# Bank_13_Bank_15_Bank_16.net
KiCad netlist of a schematic drawn in Altium Designer
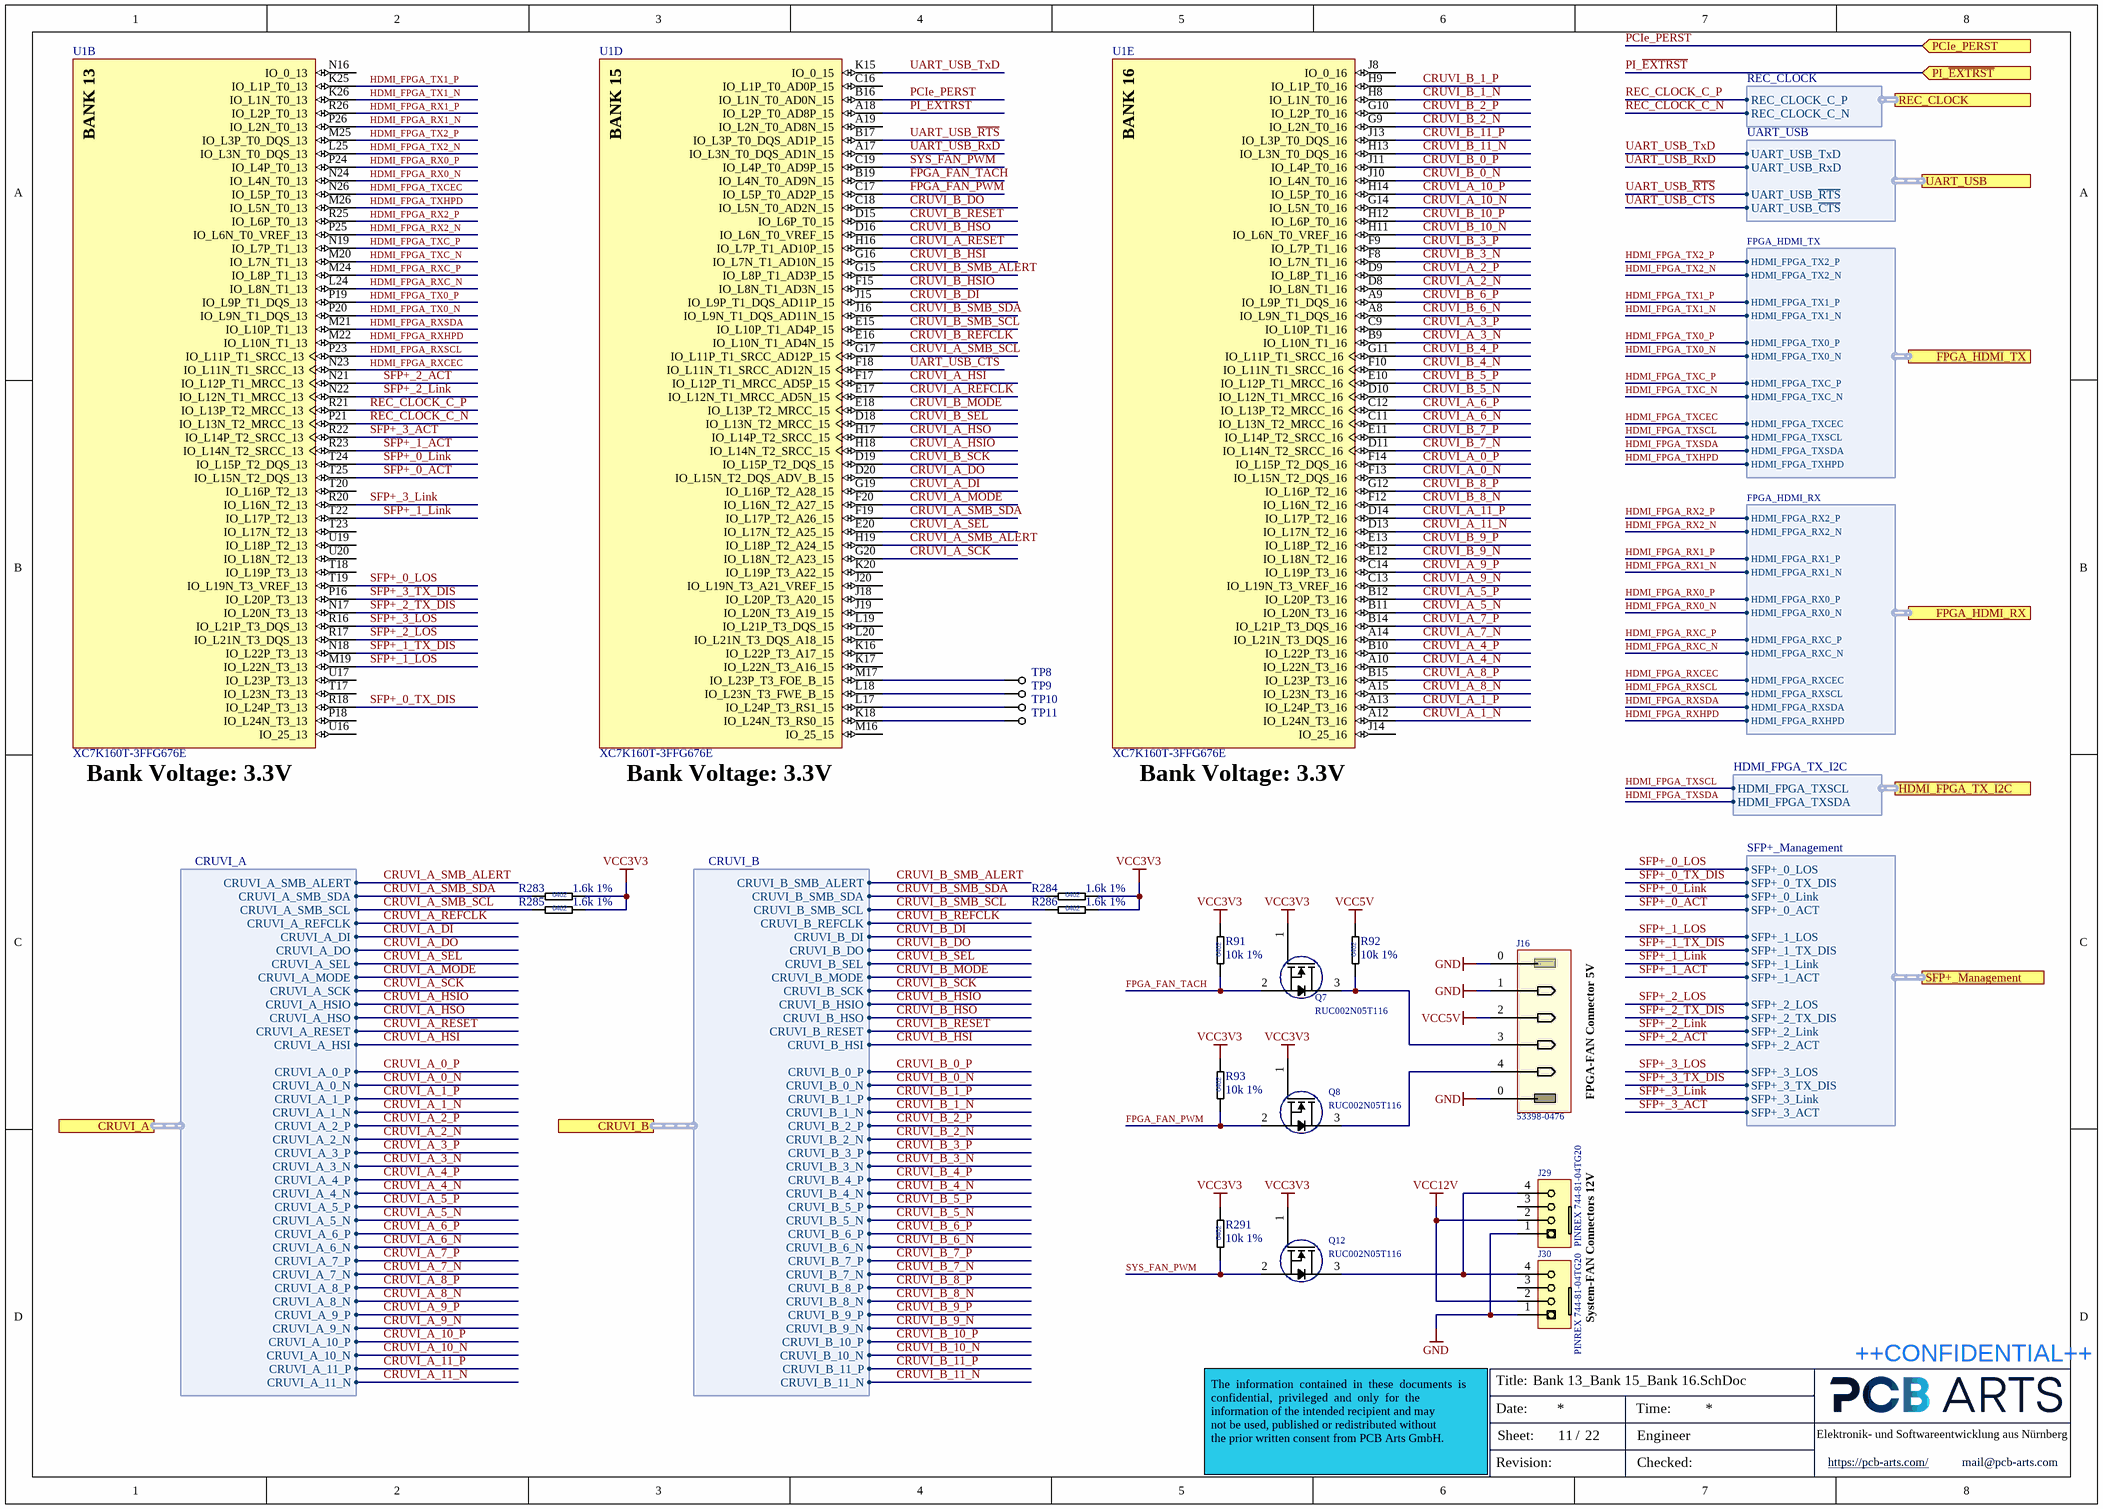
[diagram p0: Bank 13_Bank 15_Bank 16.SchDoc]

(export (version "E")
  (design (tool "Eeschema 10.0.6"))
  (components
    (comp (ref "J16")
      (value "53398-0476")
      (footprint "Conn:Molex 53398-0476")
      (description "1.25mm Pitch, PicoBlade PCB Header, Single Row, horizontal, SMD, 4 Pin")
      (libsource (lib "Conn") (part "53398-0476_1.25mm Pitch, PicoBlade PCB Header, Single Row, horizontal, SMD, 4 Pin"))
    )
    (comp (ref "J29")
      (value "PINREX 744-81-04TG20")
      (footprint "conn:PINREX 744-81-04TG20")
      (description "FAN Connector header 2.54mm 4Pol")
      (libsource (lib "Conn") (part "FAN Connector header 2.54mm 4Pol Pinrex 744-81-04TG20"))
    )
    (comp (ref "J30")
      (value "PINREX 744-81-04TG20")
      (footprint "conn:PINREX 744-81-04TG20")
      (description "FAN Connector header 2.54mm 4Pol")
      (libsource (lib "Conn") (part "FAN Connector header 2.54mm 4Pol Pinrex 744-81-04TG20"))
    )
    (comp (ref "Q7")
      (value "RUC002N05T116")
      (footprint "trans:SOT95P251X112-3N")
      (description "MOSFET N-Ch 1.2 VGS Spec")
      (libsource (lib "Trans") (part "RUC002N05T116_MOSFET N-Ch 1.2 VGS Spec"))
    )
    (comp (ref "Q8")
      (value "RUC002N05T116")
      (footprint "trans:SOT95P251X112-3N")
      (description "MOSFET N-Ch 1.2 VGS Spec")
      (libsource (lib "Trans") (part "RUC002N05T116_MOSFET N-Ch 1.2 VGS Spec"))
    )
    (comp (ref "Q12")
      (value "RUC002N05T116")
      (footprint "trans:SOT95P251X112-3N")
      (description "MOSFET N-Ch 1.2 VGS Spec")
      (libsource (lib "Trans") (part "RUC002N05T116_MOSFET N-Ch 1.2 VGS Spec"))
    )
    (comp (ref "R91")
      (value "10k 1%")
      (footprint "Res:RES_0402_L")
      (description "Thick Film Resistors - SMD 10kOhm 1%")
      (libsource (lib "Res") (part "RES_0402_10k_1%"))
    )
    (comp (ref "R92")
      (value "10k 1%")
      (footprint "Res:RES_0402_L")
      (description "Thick Film Resistors - SMD 10kOhm 1%")
      (libsource (lib "Res") (part "RES_0402_10k_1%"))
    )
    (comp (ref "R93")
      (value "10k 1%")
      (footprint "Res:RES_0402_L")
      (description "Thick Film Resistors - SMD 10kOhm 1%")
      (libsource (lib "Res") (part "RES_0402_10k_1%"))
    )
    (comp (ref "R283")
      (value "1.6k 1%")
      (footprint "Res:RES_0402_L")
      (description "Thick Film Resistors - SMD 1.6kOhm 1%")
      (libsource (lib "Res") (part "RES_0402_1.6k_1%"))
    )
    (comp (ref "R284")
      (value "1.6k 1%")
      (footprint "Res:RES_0402_L")
      (description "Thick Film Resistors - SMD 1.6kOhm 1%")
      (libsource (lib "Res") (part "RES_0402_1.6k_1%"))
    )
    (comp (ref "R285")
      (value "1.6k 1%")
      (footprint "Res:RES_0402_L")
      (description "Thick Film Resistors - SMD 1.6kOhm 1%")
      (libsource (lib "Res") (part "RES_0402_1.6k_1%"))
    )
    (comp (ref "R286")
      (value "1.6k 1%")
      (footprint "Res:RES_0402_L")
      (description "Thick Film Resistors - SMD 1.6kOhm 1%")
      (libsource (lib "Res") (part "RES_0402_1.6k_1%"))
    )
    (comp (ref "R291")
      (value "10k 1%")
      (footprint "Res:RES_0402_L")
      (description "Thick Film Resistors - SMD 10kOhm 1%")
      (libsource (lib "Res") (part "RES_0402_10k_1%"))
    )
    (comp (ref "TP8")
      (value "Testpoint")
      (footprint "Electro_mech:Testpoint 0.8mm")
      (description "Testpoint 0.8mm")
      (libsource (lib "Electro_Mech") (part "Testpoint 0.8mm"))
    )
    (comp (ref "TP9")
      (value "Testpoint")
      (footprint "Electro_mech:Testpoint 0.8mm")
      (description "Testpoint 0.8mm")
      (libsource (lib "Electro_Mech") (part "Testpoint 0.8mm"))
    )
    (comp (ref "TP10")
      (value "Testpoint")
      (footprint "Electro_mech:Testpoint 0.8mm")
      (description "Testpoint 0.8mm")
      (libsource (lib "Electro_Mech") (part "Testpoint 0.8mm"))
    )
    (comp (ref "TP11")
      (value "Testpoint")
      (footprint "Electro_mech:Testpoint 0.8mm")
      (description "Testpoint 0.8mm")
      (libsource (lib "Electro_Mech") (part "Testpoint 0.8mm"))
    )
    (comp (ref "U1")
      (value "XC7K160T-3FFG676E")
      (footprint "Digital:BGA100P2700X2700X317-676N")
      (description "Kintex-7 FPGA, 400 User I/Os, 8 GTX, 676-Ball BGA, Speed Grade 3, Extended Grade, Pb-Free")
      (libsource (lib "Digital") (part "XC7K160T-3FFG676E_Kintex-7 FPGA, 400 User I/Os, 8 GTX, FFG676"))
    )
  )
  (nets
    (net (code "9") (name "/CRUVI_A_0_N") (class "Default")
      (node (ref "U1") (pin "F13") (pinfunction "IO_L15N_T2_DQS_16_F13") (pintype "bidirectional"))
    )
    (net (code "10") (name "/CRUVI_A_0_P") (class "Default")
      (node (ref "U1") (pin "F14") (pinfunction "IO_L15P_T2_DQS_16_F14") (pintype "bidirectional"))
    )
    (net (code "11") (name "/CRUVI_A_1_N") (class "Default")
      (node (ref "U1") (pin "A12") (pinfunction "IO_L24N_T3_16_A12") (pintype "bidirectional"))
    )
    (net (code "12") (name "/CRUVI_A_1_P") (class "Default")
      (node (ref "U1") (pin "A13") (pinfunction "IO_L24P_T3_16_A13") (pintype "bidirectional"))
    )
    (net (code "13") (name "/CRUVI_A_2_N") (class "Default")
      (node (ref "U1") (pin "D8") (pinfunction "IO_L8N_T1_16_D8") (pintype "bidirectional"))
    )
    (net (code "14") (name "/CRUVI_A_2_P") (class "Default")
      (node (ref "U1") (pin "D9") (pinfunction "IO_L8P_T1_16_D9") (pintype "bidirectional"))
    )
    (net (code "15") (name "/CRUVI_A_3_N") (class "Default")
      (node (ref "U1") (pin "B9") (pinfunction "IO_L10N_T1_16_B9") (pintype "bidirectional"))
    )
    (net (code "16") (name "/CRUVI_A_3_P") (class "Default")
      (node (ref "U1") (pin "C9") (pinfunction "IO_L10P_T1_16_C9") (pintype "bidirectional"))
    )
    (net (code "17") (name "/CRUVI_A_4_N") (class "Default")
      (node (ref "U1") (pin "A10") (pinfunction "IO_L22N_T3_16_A10") (pintype "bidirectional"))
    )
    (net (code "18") (name "/CRUVI_A_4_P") (class "Default")
      (node (ref "U1") (pin "B10") (pinfunction "IO_L22P_T3_16_B10") (pintype "bidirectional"))
    )
    (net (code "19") (name "/CRUVI_A_5_N") (class "Default")
      (node (ref "U1") (pin "B11") (pinfunction "IO_L20N_T3_16_B11") (pintype "bidirectional"))
    )
    (net (code "20") (name "/CRUVI_A_5_P") (class "Default")
      (node (ref "U1") (pin "B12") (pinfunction "IO_L20P_T3_16_B12") (pintype "bidirectional"))
    )
    (net (code "21") (name "/CRUVI_A_6_N") (class "Default")
      (node (ref "U1") (pin "C11") (pinfunction "IO_L13N_T2_MRCC_16_C11") (pintype "bidirectional"))
    )
    (net (code "22") (name "/CRUVI_A_6_P") (class "Default")
      (node (ref "U1") (pin "C12") (pinfunction "IO_L13P_T2_MRCC_16_C12") (pintype "bidirectional"))
    )
    (net (code "23") (name "/CRUVI_A_7_N") (class "Default")
      (node (ref "U1") (pin "A14") (pinfunction "IO_L21N_T3_DQS_16_A14") (pintype "bidirectional"))
    )
    (net (code "24") (name "/CRUVI_A_7_P") (class "Default")
      (node (ref "U1") (pin "B14") (pinfunction "IO_L21P_T3_DQS_16_B14") (pintype "bidirectional"))
    )
    (net (code "25") (name "/CRUVI_A_8_N") (class "Default")
      (node (ref "U1") (pin "A15") (pinfunction "IO_L23N_T3_16_A15") (pintype "bidirectional"))
    )
    (net (code "26") (name "/CRUVI_A_8_P") (class "Default")
      (node (ref "U1") (pin "B15") (pinfunction "IO_L23P_T3_16_B15") (pintype "bidirectional"))
    )
    (net (code "27") (name "/CRUVI_A_9_N") (class "Default")
      (node (ref "U1") (pin "C13") (pinfunction "IO_L19N_T3_VREF_16_C13") (pintype "bidirectional"))
    )
    (net (code "28") (name "/CRUVI_A_9_P") (class "Default")
      (node (ref "U1") (pin "C14") (pinfunction "IO_L19P_T3_16_C14") (pintype "bidirectional"))
    )
    (net (code "29") (name "/CRUVI_A_10_N") (class "Default")
      (node (ref "U1") (pin "G14") (pinfunction "IO_L5N_T0_16_G14") (pintype "bidirectional"))
    )
    (net (code "30") (name "/CRUVI_A_10_P") (class "Default")
      (node (ref "U1") (pin "H14") (pinfunction "IO_L5P_T0_16_H14") (pintype "bidirectional"))
    )
    (net (code "31") (name "/CRUVI_A_11_N") (class "Default")
      (node (ref "U1") (pin "D13") (pinfunction "IO_L17N_T2_16_D13") (pintype "bidirectional"))
    )
    (net (code "32") (name "/CRUVI_A_11_P") (class "Default")
      (node (ref "U1") (pin "D14") (pinfunction "IO_L17P_T2_16_D14") (pintype "bidirectional"))
    )
    (net (code "33") (name "/CRUVI_A_DI") (class "Default")
      (node (ref "U1") (pin "G19") (pinfunction "IO_L16P_T2_A28_15_G19") (pintype "bidirectional"))
    )
    (net (code "34") (name "/CRUVI_A_DO") (class "Default")
      (node (ref "U1") (pin "D20") (pinfunction "IO_L15N_T2_DQS_ADV_B_15_D20") (pintype "bidirectional"))
    )
    (net (code "35") (name "/CRUVI_A_HSI") (class "Default")
      (node (ref "U1") (pin "F17") (pinfunction "IO_L12P_T1_MRCC_AD5P_15_F17") (pintype "bidirectional"))
    )
    (net (code "36") (name "/CRUVI_A_HSIO") (class "Default")
      (node (ref "U1") (pin "H18") (pinfunction "IO_L14N_T2_SRCC_15_H18") (pintype "bidirectional"))
    )
    (net (code "37") (name "/CRUVI_A_HSO") (class "Default")
      (node (ref "U1") (pin "H17") (pinfunction "IO_L14P_T2_SRCC_15_H17") (pintype "bidirectional"))
    )
    (net (code "38") (name "/CRUVI_A_MODE") (class "Default")
      (node (ref "U1") (pin "F20") (pinfunction "IO_L16N_T2_A27_15_F20") (pintype "bidirectional"))
    )
    (net (code "39") (name "/CRUVI_A_REFCLK") (class "Default")
      (node (ref "U1") (pin "E17") (pinfunction "IO_L12N_T1_MRCC_AD5N_15_E17") (pintype "bidirectional"))
    )
    (net (code "40") (name "/CRUVI_A_RESET") (class "Default")
      (node (ref "U1") (pin "H16") (pinfunction "IO_L7P_T1_AD10P_15_H16") (pintype "bidirectional"))
    )
    (net (code "41") (name "/CRUVI_A_SCK") (class "Default")
      (node (ref "U1") (pin "G20") (pinfunction "IO_L18N_T2_A23_15_G20") (pintype "bidirectional"))
    )
    (net (code "42") (name "/CRUVI_A_SEL") (class "Default")
      (node (ref "U1") (pin "E20") (pinfunction "IO_L17N_T2_A25_15_E20") (pintype "bidirectional"))
    )
    (net (code "43") (name "/CRUVI_A_SMB_ALERT") (class "Default")
      (node (ref "U1") (pin "H19") (pinfunction "IO_L18P_T2_A24_15_H19") (pintype "bidirectional"))
    )
    (net (code "44") (name "/CRUVI_A_SMB_SCL") (class "Default")
      (node (ref "R285") (pin "1") (pinfunction "1_1") (pintype "passive"))
      (node (ref "U1") (pin "G17") (pinfunction "IO_L11P_T1_SRCC_AD12P_15_G17") (pintype "bidirectional"))
    )
    (net (code "45") (name "/CRUVI_A_SMB_SDA") (class "Default")
      (node (ref "R283") (pin "1") (pinfunction "1_1") (pintype "passive"))
      (node (ref "U1") (pin "F19") (pinfunction "IO_L17P_T2_A26_15_F19") (pintype "bidirectional"))
    )
    (net (code "46") (name "/CRUVI_B_0_N") (class "Default")
      (node (ref "U1") (pin "J10") (pinfunction "IO_L4N_T0_16_J10") (pintype "bidirectional"))
    )
    (net (code "47") (name "/CRUVI_B_0_P") (class "Default")
      (node (ref "U1") (pin "J11") (pinfunction "IO_L4P_T0_16_J11") (pintype "bidirectional"))
    )
    (net (code "48") (name "/CRUVI_B_1_N") (class "Default")
      (node (ref "U1") (pin "H8") (pinfunction "IO_L1N_T0_16_H8") (pintype "bidirectional"))
    )
    (net (code "49") (name "/CRUVI_B_1_P") (class "Default")
      (node (ref "U1") (pin "H9") (pinfunction "IO_L1P_T0_16_H9") (pintype "bidirectional"))
    )
    (net (code "50") (name "/CRUVI_B_2_N") (class "Default")
      (node (ref "U1") (pin "G9") (pinfunction "IO_L2N_T0_16_G9") (pintype "bidirectional"))
    )
    (net (code "51") (name "/CRUVI_B_2_P") (class "Default")
      (node (ref "U1") (pin "G10") (pinfunction "IO_L2P_T0_16_G10") (pintype "bidirectional"))
    )
    (net (code "52") (name "/CRUVI_B_3_N") (class "Default")
      (node (ref "U1") (pin "F8") (pinfunction "IO_L7N_T1_16_F8") (pintype "bidirectional"))
    )
    (net (code "53") (name "/CRUVI_B_3_P") (class "Default")
      (node (ref "U1") (pin "F9") (pinfunction "IO_L7P_T1_16_F9") (pintype "bidirectional"))
    )
    (net (code "54") (name "/CRUVI_B_4_N") (class "Default")
      (node (ref "U1") (pin "F10") (pinfunction "IO_L11N_T1_SRCC_16_F10") (pintype "bidirectional"))
    )
    (net (code "55") (name "/CRUVI_B_4_P") (class "Default")
      (node (ref "U1") (pin "G11") (pinfunction "IO_L11P_T1_SRCC_16_G11") (pintype "bidirectional"))
    )
    (net (code "56") (name "/CRUVI_B_5_N") (class "Default")
      (node (ref "U1") (pin "D10") (pinfunction "IO_L12N_T1_MRCC_16_D10") (pintype "bidirectional"))
    )
    (net (code "57") (name "/CRUVI_B_5_P") (class "Default")
      (node (ref "U1") (pin "E10") (pinfunction "IO_L12P_T1_MRCC_16_E10") (pintype "bidirectional"))
    )
    (net (code "58") (name "/CRUVI_B_6_N") (class "Default")
      (node (ref "U1") (pin "A8") (pinfunction "IO_L9N_T1_DQS_16_A8") (pintype "bidirectional"))
    )
    (net (code "59") (name "/CRUVI_B_6_P") (class "Default")
      (node (ref "U1") (pin "A9") (pinfunction "IO_L9P_T1_DQS_16_A9") (pintype "bidirectional"))
    )
    (net (code "60") (name "/CRUVI_B_7_N") (class "Default")
      (node (ref "U1") (pin "D11") (pinfunction "IO_L14N_T2_SRCC_16_D11") (pintype "bidirectional"))
    )
    (net (code "61") (name "/CRUVI_B_7_P") (class "Default")
      (node (ref "U1") (pin "E11") (pinfunction "IO_L14P_T2_SRCC_16_E11") (pintype "bidirectional"))
    )
    (net (code "62") (name "/CRUVI_B_8_N") (class "Default")
      (node (ref "U1") (pin "F12") (pinfunction "IO_L16N_T2_16_F12") (pintype "bidirectional"))
    )
    (net (code "63") (name "/CRUVI_B_8_P") (class "Default")
      (node (ref "U1") (pin "G12") (pinfunction "IO_L16P_T2_16_G12") (pintype "bidirectional"))
    )
    (net (code "64") (name "/CRUVI_B_9_N") (class "Default")
      (node (ref "U1") (pin "E12") (pinfunction "IO_L18N_T2_16_E12") (pintype "bidirectional"))
    )
    (net (code "65") (name "/CRUVI_B_9_P") (class "Default")
      (node (ref "U1") (pin "E13") (pinfunction "IO_L18P_T2_16_E13") (pintype "bidirectional"))
    )
    (net (code "66") (name "/CRUVI_B_10_N") (class "Default")
      (node (ref "U1") (pin "H11") (pinfunction "IO_L6N_T0_VREF_16_H11") (pintype "bidirectional"))
    )
    (net (code "67") (name "/CRUVI_B_10_P") (class "Default")
      (node (ref "U1") (pin "H12") (pinfunction "IO_L6P_T0_16_H12") (pintype "bidirectional"))
    )
    (net (code "68") (name "/CRUVI_B_11_N") (class "Default")
      (node (ref "U1") (pin "H13") (pinfunction "IO_L3N_T0_DQS_16_H13") (pintype "bidirectional"))
    )
    (net (code "69") (name "/CRUVI_B_11_P") (class "Default")
      (node (ref "U1") (pin "J13") (pinfunction "IO_L3P_T0_DQS_16_J13") (pintype "bidirectional"))
    )
    (net (code "70") (name "/CRUVI_B_DI") (class "Default")
      (node (ref "U1") (pin "J15") (pinfunction "IO_L9P_T1_DQS_AD11P_15_J15") (pintype "bidirectional"))
    )
    (net (code "71") (name "/CRUVI_B_DO") (class "Default")
      (node (ref "U1") (pin "C18") (pinfunction "IO_L5N_T0_AD2N_15_C18") (pintype "bidirectional"))
    )
    (net (code "72") (name "/CRUVI_B_HSI") (class "Default")
      (node (ref "U1") (pin "G16") (pinfunction "IO_L7N_T1_AD10N_15_G16") (pintype "bidirectional"))
    )
    (net (code "73") (name "/CRUVI_B_HSIO") (class "Default")
      (node (ref "U1") (pin "F15") (pinfunction "IO_L8N_T1_AD3N_15_F15") (pintype "bidirectional"))
    )
    (net (code "74") (name "/CRUVI_B_HSO") (class "Default")
      (node (ref "U1") (pin "D16") (pinfunction "IO_L6N_T0_VREF_15_D16") (pintype "bidirectional"))
    )
    (net (code "75") (name "/CRUVI_B_MODE") (class "Default")
      (node (ref "U1") (pin "E18") (pinfunction "IO_L13P_T2_MRCC_15_E18") (pintype "bidirectional"))
    )
    (net (code "76") (name "/CRUVI_B_REFCLK") (class "Default")
      (node (ref "U1") (pin "E16") (pinfunction "IO_L10N_T1_AD4N_15_E16") (pintype "bidirectional"))
    )
    (net (code "77") (name "/CRUVI_B_RESET") (class "Default")
      (node (ref "U1") (pin "D15") (pinfunction "IO_L6P_T0_15_D15") (pintype "bidirectional"))
    )
    (net (code "78") (name "/CRUVI_B_SCK") (class "Default")
      (node (ref "U1") (pin "D19") (pinfunction "IO_L15P_T2_DQS_15_D19") (pintype "bidirectional"))
    )
    (net (code "79") (name "/CRUVI_B_SEL") (class "Default")
      (node (ref "U1") (pin "D18") (pinfunction "IO_L13N_T2_MRCC_15_D18") (pintype "bidirectional"))
    )
    (net (code "80") (name "/CRUVI_B_SMB_ALERT") (class "Default")
      (node (ref "U1") (pin "G15") (pinfunction "IO_L8P_T1_AD3P_15_G15") (pintype "bidirectional"))
    )
    (net (code "81") (name "/CRUVI_B_SMB_SCL") (class "Default")
      (node (ref "R286") (pin "1") (pinfunction "1_1") (pintype "passive"))
      (node (ref "U1") (pin "E15") (pinfunction "IO_L10P_T1_AD4P_15_E15") (pintype "bidirectional"))
    )
    (net (code "82") (name "/CRUVI_B_SMB_SDA") (class "Default")
      (node (ref "R284") (pin "1") (pinfunction "1_1") (pintype "passive"))
      (node (ref "U1") (pin "J16") (pinfunction "IO_L9N_T1_DQS_AD11N_15_J16") (pintype "bidirectional"))
    )
    (net (code "83") (name "/FPGA_FAN_PWM") (class "Default")
      (node (ref "Q8") (pin "2") (pinfunction "D_2") (pintype "passive"))
      (node (ref "R93") (pin "1") (pinfunction "1_1") (pintype "passive"))
      (node (ref "U1") (pin "C17") (pinfunction "IO_L5P_T0_AD2P_15_C17") (pintype "bidirectional"))
    )
    (net (code "84") (name "/FPGA_FAN_TACH") (class "Default")
      (node (ref "Q7") (pin "2") (pinfunction "D_2") (pintype "passive"))
      (node (ref "R91") (pin "1") (pinfunction "1_1") (pintype "passive"))
      (node (ref "U1") (pin "B19") (pinfunction "IO_L4N_T0_AD9N_15_B19") (pintype "bidirectional"))
    )
    (net (code "85") (name "/HDMI_FPGA_RX0_N") (class "Default")
      (node (ref "U1") (pin "N24") (pinfunction "IO_L4N_T0_13_N24") (pintype "bidirectional"))
    )
    (net (code "86") (name "/HDMI_FPGA_RX0_P") (class "Default")
      (node (ref "U1") (pin "P24") (pinfunction "IO_L4P_T0_13_P24") (pintype "bidirectional"))
    )
    (net (code "87") (name "/HDMI_FPGA_RX1_N") (class "Default")
      (node (ref "U1") (pin "P26") (pinfunction "IO_L2N_T0_13_P26") (pintype "bidirectional"))
    )
    (net (code "88") (name "/HDMI_FPGA_RX1_P") (class "Default")
      (node (ref "U1") (pin "R26") (pinfunction "IO_L2P_T0_13_R26") (pintype "bidirectional"))
    )
    (net (code "89") (name "/HDMI_FPGA_RX2_N") (class "Default")
      (node (ref "U1") (pin "P25") (pinfunction "IO_L6N_T0_VREF_13_P25") (pintype "bidirectional"))
    )
    (net (code "90") (name "/HDMI_FPGA_RX2_P") (class "Default")
      (node (ref "U1") (pin "R25") (pinfunction "IO_L6P_T0_13_R25") (pintype "bidirectional"))
    )
    (net (code "91") (name "/HDMI_FPGA_RXCEC") (class "Default")
      (node (ref "U1") (pin "N23") (pinfunction "IO_L11N_T1_SRCC_13_N23") (pintype "bidirectional"))
    )
    (net (code "92") (name "/HDMI_FPGA_RXC_N") (class "Default")
      (node (ref "U1") (pin "L24") (pinfunction "IO_L8N_T1_13_L24") (pintype "bidirectional"))
    )
    (net (code "93") (name "/HDMI_FPGA_RXC_P") (class "Default")
      (node (ref "U1") (pin "M24") (pinfunction "IO_L8P_T1_13_M24") (pintype "bidirectional"))
    )
    (net (code "94") (name "/HDMI_FPGA_RXHPD") (class "Default")
      (node (ref "U1") (pin "M22") (pinfunction "IO_L10N_T1_13_M22") (pintype "bidirectional"))
    )
    (net (code "95") (name "/HDMI_FPGA_RXSCL") (class "Default")
      (node (ref "U1") (pin "P23") (pinfunction "IO_L11P_T1_SRCC_13_P23") (pintype "bidirectional"))
    )
    (net (code "96") (name "/HDMI_FPGA_RXSDA") (class "Default")
      (node (ref "U1") (pin "M21") (pinfunction "IO_L10P_T1_13_M21") (pintype "bidirectional"))
    )
    (net (code "97") (name "/HDMI_FPGA_TX0_N") (class "Default")
      (node (ref "U1") (pin "P20") (pinfunction "IO_L9N_T1_DQS_13_P20") (pintype "bidirectional"))
    )
    (net (code "98") (name "/HDMI_FPGA_TX0_P") (class "Default")
      (node (ref "U1") (pin "P19") (pinfunction "IO_L9P_T1_DQS_13_P19") (pintype "bidirectional"))
    )
    (net (code "99") (name "/HDMI_FPGA_TX1_N") (class "Default")
      (node (ref "U1") (pin "K26") (pinfunction "IO_L1N_T0_13_K26") (pintype "bidirectional"))
    )
    (net (code "100") (name "/HDMI_FPGA_TX1_P") (class "Default")
      (node (ref "U1") (pin "K25") (pinfunction "IO_L1P_T0_13_K25") (pintype "bidirectional"))
    )
    (net (code "101") (name "/HDMI_FPGA_TX2_N") (class "Default")
      (node (ref "U1") (pin "L25") (pinfunction "IO_L3N_T0_DQS_13_L25") (pintype "bidirectional"))
    )
    (net (code "102") (name "/HDMI_FPGA_TX2_P") (class "Default")
      (node (ref "U1") (pin "M25") (pinfunction "IO_L3P_T0_DQS_13_M25") (pintype "bidirectional"))
    )
    (net (code "103") (name "/HDMI_FPGA_TXCEC") (class "Default")
      (node (ref "U1") (pin "N26") (pinfunction "IO_L5P_T0_13_N26") (pintype "bidirectional"))
    )
    (net (code "104") (name "/HDMI_FPGA_TXC_N") (class "Default")
      (node (ref "U1") (pin "M20") (pinfunction "IO_L7N_T1_13_M20") (pintype "bidirectional"))
    )
    (net (code "105") (name "/HDMI_FPGA_TXC_P") (class "Default")
      (node (ref "U1") (pin "N19") (pinfunction "IO_L7P_T1_13_N19") (pintype "bidirectional"))
    )
    (net (code "106") (name "/HDMI_FPGA_TXHPD") (class "Default")
      (node (ref "U1") (pin "M26") (pinfunction "IO_L5N_T0_13_M26") (pintype "bidirectional"))
    )
    (net (code "109") (name "/PCIe_PERST") (class "Default")
      (node (ref "U1") (pin "B16") (pinfunction "IO_L1N_T0_AD0N_15_B16") (pintype "bidirectional"))
    )
    (net (code "110") (name "/PI_~{EXTRST}") (class "Default")
      (node (ref "U1") (pin "A18") (pinfunction "IO_L2P_T0_AD8P_15_A18") (pintype "bidirectional"))
    )
    (net (code "111") (name "/REC_CLOCK_C_N") (class "Default")
      (node (ref "U1") (pin "P21") (pinfunction "IO_L13N_T2_MRCC_13_P21") (pintype "bidirectional"))
    )
    (net (code "112") (name "/REC_CLOCK_C_P") (class "Default")
      (node (ref "U1") (pin "R21") (pinfunction "IO_L13P_T2_MRCC_13_R21") (pintype "bidirectional"))
    )
    (net (code "113") (name "/SFP+_0_ACT") (class "Default")
      (node (ref "U1") (pin "T25") (pinfunction "IO_L15N_T2_DQS_13_T25") (pintype "bidirectional"))
    )
    (net (code "114") (name "/SFP+_0_LOS") (class "Default")
      (node (ref "U1") (pin "T19") (pinfunction "IO_L19N_T3_VREF_13_T19") (pintype "bidirectional"))
    )
    (net (code "115") (name "/SFP+_0_Link") (class "Default")
      (node (ref "U1") (pin "T24") (pinfunction "IO_L15P_T2_DQS_13_T24") (pintype "bidirectional"))
    )
    (net (code "116") (name "/SFP+_0_TX_DIS") (class "Default")
      (node (ref "U1") (pin "R18") (pinfunction "IO_L24P_T3_13_R18") (pintype "bidirectional"))
    )
    (net (code "117") (name "/SFP+_1_ACT") (class "Default")
      (node (ref "U1") (pin "R23") (pinfunction "IO_L14N_T2_SRCC_13_R23") (pintype "bidirectional"))
    )
    (net (code "118") (name "/SFP+_1_LOS") (class "Default")
      (node (ref "U1") (pin "M19") (pinfunction "IO_L22N_T3_13_M19") (pintype "bidirectional"))
    )
    (net (code "119") (name "/SFP+_1_Link") (class "Default")
      (node (ref "U1") (pin "T22") (pinfunction "IO_L17P_T2_13_T22") (pintype "bidirectional"))
    )
    (net (code "120") (name "/SFP+_1_TX_DIS") (class "Default")
      (node (ref "U1") (pin "N18") (pinfunction "IO_L22P_T3_13_N18") (pintype "bidirectional"))
    )
    (net (code "121") (name "/SFP+_2_ACT") (class "Default")
      (node (ref "U1") (pin "N21") (pinfunction "IO_L12P_T1_MRCC_13_N21") (pintype "bidirectional"))
    )
    (net (code "122") (name "/SFP+_2_LOS") (class "Default")
      (node (ref "U1") (pin "R17") (pinfunction "IO_L21N_T3_DQS_13_R17") (pintype "bidirectional"))
    )
    (net (code "123") (name "/SFP+_2_Link") (class "Default")
      (node (ref "U1") (pin "N22") (pinfunction "IO_L12N_T1_MRCC_13_N22") (pintype "bidirectional"))
    )
    (net (code "124") (name "/SFP+_2_TX_DIS") (class "Default")
      (node (ref "U1") (pin "N17") (pinfunction "IO_L20N_T3_13_N17") (pintype "bidirectional"))
    )
    (net (code "125") (name "/SFP+_3_ACT") (class "Default")
      (node (ref "U1") (pin "R22") (pinfunction "IO_L14P_T2_SRCC_13_R22") (pintype "bidirectional"))
    )
    (net (code "126") (name "/SFP+_3_LOS") (class "Default")
      (node (ref "U1") (pin "R16") (pinfunction "IO_L21P_T3_DQS_13_R16") (pintype "bidirectional"))
    )
    (net (code "127") (name "/SFP+_3_Link") (class "Default")
      (node (ref "U1") (pin "R20") (pinfunction "IO_L16N_T2_13_R20") (pintype "bidirectional"))
    )
    (net (code "128") (name "/SFP+_3_TX_DIS") (class "Default")
      (node (ref "U1") (pin "P16") (pinfunction "IO_L20P_T3_13_P16") (pintype "bidirectional"))
    )
    (net (code "129") (name "/SYS_FAN_PWM") (class "Default")
      (node (ref "Q12") (pin "2") (pinfunction "D_2") (pintype "passive"))
      (node (ref "R291") (pin "1") (pinfunction "1_1") (pintype "passive"))
      (node (ref "U1") (pin "C19") (pinfunction "IO_L4P_T0_AD9P_15_C19") (pintype "bidirectional"))
    )
    (net (code "130") (name "/UART_USB_RxD") (class "Default")
      (node (ref "U1") (pin "A17") (pinfunction "IO_L3N_T0_DQS_AD1N_15_A17") (pintype "bidirectional"))
    )
    (net (code "131") (name "/UART_USB_TxD") (class "Default")
      (node (ref "U1") (pin "K15") (pinfunction "IO_0_15_K15") (pintype "bidirectional"))
    )
    (net (code "132") (name "/UART_USB_~{CTS}") (class "Default")
      (node (ref "U1") (pin "F18") (pinfunction "IO_L11N_T1_SRCC_AD12N_15_F18") (pintype "bidirectional"))
    )
    (net (code "133") (name "/UART_USB_~{RTS}") (class "Default")
      (node (ref "U1") (pin "B17") (pinfunction "IO_L3P_T0_DQS_AD1P_15_B17") (pintype "bidirectional"))
    )
    (net (code "142") (name "GND") (class "Default")
      (node (ref "J16") (pin "0") (pinfunction "0_0") (pintype "passive"))
      (node (ref "J16") (pin "1") (pinfunction "1_1") (pintype "passive"))
      (node (ref "J29") (pin "1") (pinfunction "1_1") (pintype "passive"))
      (node (ref "J30") (pin "1") (pinfunction "1_1") (pintype "passive"))
    )
    (net (code "143") (name "Net-(Q7-S)") (class "Default")
      (node (ref "J16") (pin "3") (pinfunction "3_3") (pintype "passive"))
      (node (ref "Q7") (pin "3") (pinfunction "S_3") (pintype "passive"))
      (node (ref "R92") (pin "1") (pinfunction "1_1") (pintype "passive"))
    )
    (net (code "144") (name "Net-(Q8-S)") (class "Default")
      (node (ref "J16") (pin "4") (pinfunction "4_4") (pintype "passive"))
      (node (ref "Q8") (pin "3") (pinfunction "S_3") (pintype "passive"))
    )
    (net (code "145") (name "Net-(Q12-S)") (class "Default")
      (node (ref "J29") (pin "4") (pinfunction "4_4") (pintype "passive"))
      (node (ref "J30") (pin "4") (pinfunction "4_4") (pintype "passive"))
      (node (ref "Q12") (pin "3") (pinfunction "S_3") (pintype "passive"))
    )
    (net (code "146") (name "Net-(TP8-GND)") (class "Default")
      (node (ref "TP8") (pin "1") (pinfunction "GND_1") (pintype "passive"))
      (node (ref "U1") (pin "M17") (pinfunction "IO_L23P_T3_FOE_B_15_M17") (pintype "bidirectional"))
    )
    (net (code "147") (name "Net-(TP9-GND)") (class "Default")
      (node (ref "TP9") (pin "1") (pinfunction "GND_1") (pintype "passive"))
      (node (ref "U1") (pin "L18") (pinfunction "IO_L23N_T3_FWE_B_15_L18") (pintype "bidirectional"))
    )
    (net (code "148") (name "Net-(TP10-GND)") (class "Default")
      (node (ref "TP10") (pin "1") (pinfunction "GND_1") (pintype "passive"))
      (node (ref "U1") (pin "L17") (pinfunction "IO_L24P_T3_RS1_15_L17") (pintype "bidirectional"))
    )
    (net (code "149") (name "Net-(TP11-GND)") (class "Default")
      (node (ref "TP11") (pin "1") (pinfunction "GND_1") (pintype "passive"))
      (node (ref "U1") (pin "K18") (pinfunction "IO_L24N_T3_RS0_15_K18") (pintype "bidirectional"))
    )
    (net (code "150") (name "VCC3V3") (class "Default")
      (node (ref "Q12") (pin "1") (pinfunction "G_1") (pintype "passive"))
      (node (ref "Q7") (pin "1") (pinfunction "G_1") (pintype "passive"))
      (node (ref "Q8") (pin "1") (pinfunction "G_1") (pintype "passive"))
      (node (ref "R283") (pin "2") (pinfunction "2_2") (pintype "passive"))
      (node (ref "R284") (pin "2") (pinfunction "2_2") (pintype "passive"))
      (node (ref "R285") (pin "2") (pinfunction "2_2") (pintype "passive"))
      (node (ref "R286") (pin "2") (pinfunction "2_2") (pintype "passive"))
      (node (ref "R291") (pin "2") (pinfunction "2_2") (pintype "passive"))
      (node (ref "R91") (pin "2") (pinfunction "2_2") (pintype "passive"))
      (node (ref "R93") (pin "2") (pinfunction "2_2") (pintype "passive"))
    )
    (net (code "151") (name "VCC5V") (class "Default")
      (node (ref "J16") (pin "2") (pinfunction "2_2") (pintype "passive"))
      (node (ref "R92") (pin "2") (pinfunction "2_2") (pintype "passive"))
    )
    (net (code "152") (name "VCC12V") (class "Default")
      (node (ref "J29") (pin "2") (pinfunction "2_2") (pintype "passive"))
      (node (ref "J30") (pin "2") (pinfunction "2_2") (pintype "passive"))
    )
    (net (code "153") (name "unconnected-(J29-Pad3)") (class "Default")
      (node (ref "J29") (pin "3") (pinfunction "3_3") (pintype "passive"))
    )
    (net (code "154") (name "unconnected-(J30-Pad3)") (class "Default")
      (node (ref "J30") (pin "3") (pinfunction "3_3") (pintype "passive"))
    )
    (net (code "155") (name "unconnected-(U1B-IO_0_13-PadN16)") (class "Default")
      (node (ref "U1") (pin "N16") (pinfunction "IO_0_13_N16") (pintype "bidirectional"))
    )
    (net (code "156") (name "unconnected-(U1B-IO_25_13-PadU16)") (class "Default")
      (node (ref "U1") (pin "U16") (pinfunction "IO_25_13_U16") (pintype "bidirectional"))
    )
    (net (code "157") (name "unconnected-(U1B-IO_L16P_T2_13-PadT20)") (class "Default")
      (node (ref "U1") (pin "T20") (pinfunction "IO_L16P_T2_13_T20") (pintype "bidirectional"))
    )
    (net (code "158") (name "unconnected-(U1B-IO_L17N_T2_13-PadT23)") (class "Default")
      (node (ref "U1") (pin "T23") (pinfunction "IO_L17N_T2_13_T23") (pintype "bidirectional"))
    )
    (net (code "159") (name "unconnected-(U1B-IO_L18N_T2_13-PadU20)") (class "Default")
      (node (ref "U1") (pin "U20") (pinfunction "IO_L18N_T2_13_U20") (pintype "bidirectional"))
    )
    (net (code "160") (name "unconnected-(U1B-IO_L18P_T2_13-PadU19)") (class "Default")
      (node (ref "U1") (pin "U19") (pinfunction "IO_L18P_T2_13_U19") (pintype "bidirectional"))
    )
    (net (code "161") (name "unconnected-(U1B-IO_L19P_T3_13-PadT18)") (class "Default")
      (node (ref "U1") (pin "T18") (pinfunction "IO_L19P_T3_13_T18") (pintype "bidirectional"))
    )
    (net (code "162") (name "unconnected-(U1B-IO_L23N_T3_13-PadT17)") (class "Default")
      (node (ref "U1") (pin "T17") (pinfunction "IO_L23N_T3_13_T17") (pintype "bidirectional"))
    )
    (net (code "163") (name "unconnected-(U1B-IO_L23P_T3_13-PadU17)") (class "Default")
      (node (ref "U1") (pin "U17") (pinfunction "IO_L23P_T3_13_U17") (pintype "bidirectional"))
    )
    (net (code "164") (name "unconnected-(U1B-IO_L24N_T3_13-PadP18)") (class "Default")
      (node (ref "U1") (pin "P18") (pinfunction "IO_L24N_T3_13_P18") (pintype "bidirectional"))
    )
    (net (code "165") (name "unconnected-(U1D-IO_25_15-PadM16)") (class "Default")
      (node (ref "U1") (pin "M16") (pinfunction "IO_25_15_M16") (pintype "bidirectional"))
    )
    (net (code "166") (name "unconnected-(U1D-IO_L1P_T0_AD0P_15-PadC16)") (class "Default")
      (node (ref "U1") (pin "C16") (pinfunction "IO_L1P_T0_AD0P_15_C16") (pintype "bidirectional"))
    )
    (net (code "167") (name "unconnected-(U1D-IO_L2N_T0_AD8N_15-PadA19)") (class "Default")
      (node (ref "U1") (pin "A19") (pinfunction "IO_L2N_T0_AD8N_15_A19") (pintype "bidirectional"))
    )
    (net (code "168") (name "unconnected-(U1D-IO_L19N_T3_A21_VREF_15-PadJ20)") (class "Default")
      (node (ref "U1") (pin "J20") (pinfunction "IO_L19N_T3_A21_VREF_15_J20") (pintype "bidirectional"))
    )
    (net (code "169") (name "unconnected-(U1D-IO_L19P_T3_A22_15-PadK20)") (class "Default")
      (node (ref "U1") (pin "K20") (pinfunction "IO_L19P_T3_A22_15_K20") (pintype "bidirectional"))
    )
    (net (code "170") (name "unconnected-(U1D-IO_L20N_T3_A19_15-PadJ19)") (class "Default")
      (node (ref "U1") (pin "J19") (pinfunction "IO_L20N_T3_A19_15_J19") (pintype "bidirectional"))
    )
    (net (code "171") (name "unconnected-(U1D-IO_L20P_T3_A20_15-PadJ18)") (class "Default")
      (node (ref "U1") (pin "J18") (pinfunction "IO_L20P_T3_A20_15_J18") (pintype "bidirectional"))
    )
    (net (code "172") (name "unconnected-(U1D-IO_L21N_T3_DQS_A18_15-PadL20)") (class "Default")
      (node (ref "U1") (pin "L20") (pinfunction "IO_L21N_T3_DQS_A18_15_L20") (pintype "bidirectional"))
    )
    (net (code "173") (name "unconnected-(U1D-IO_L21P_T3_DQS_15-PadL19)") (class "Default")
      (node (ref "U1") (pin "L19") (pinfunction "IO_L21P_T3_DQS_15_L19") (pintype "bidirectional"))
    )
    (net (code "174") (name "unconnected-(U1D-IO_L22N_T3_A16_15-PadK17)") (class "Default")
      (node (ref "U1") (pin "K17") (pinfunction "IO_L22N_T3_A16_15_K17") (pintype "bidirectional"))
    )
    (net (code "175") (name "unconnected-(U1D-IO_L22P_T3_A17_15-PadK16)") (class "Default")
      (node (ref "U1") (pin "K16") (pinfunction "IO_L22P_T3_A17_15_K16") (pintype "bidirectional"))
    )
    (net (code "176") (name "unconnected-(U1E-IO_0_16-PadJ8)") (class "Default")
      (node (ref "U1") (pin "J8") (pinfunction "IO_0_16_J8") (pintype "bidirectional"))
    )
    (net (code "177") (name "unconnected-(U1E-IO_25_16-PadJ14)") (class "Default")
      (node (ref "U1") (pin "J14") (pinfunction "IO_25_16_J14") (pintype "bidirectional"))
    )
  )
)
